# mux-break.net
KiCad netlist of a schematic drawn in EAGLE
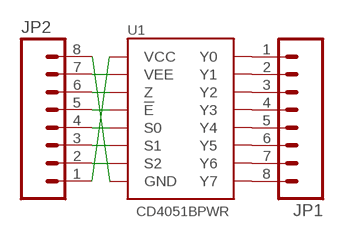
[diagram p0: schematic, sheet 1]

(export (version "E")
  (design (tool "Eeschema 10.0.6"))
  (components
    (comp (ref "JP1")
      (value "M08SILK_FEMALE_PTH")
      (footprint "eagle-import:1X08")
      (libsource (lib "eagle-import") (part "M08SILK_FEMALE_PTH"))
    )
    (comp (ref "JP2")
      (value "M08SILK_FEMALE_PTH")
      (footprint "eagle-import:1X08")
      (libsource (lib "eagle-import") (part "M08SILK_FEMALE_PTH"))
    )
    (comp (ref "U1")
      (value "CD4051BPWR")
      (footprint "eagle-import:TSSOP-16")
      (libsource (lib "eagle-import") (part "CD4051BPWR"))
    )
  )
  (nets
    (net (code "1") (name "Net-(U1-GND)") (class "Default")
      (node (ref "JP2") (pin "8") (pinfunction "8_8") (pintype "passive"))
      (node (ref "U1") (pin "P$8") (pinfunction "GND_P$8") (pintype "bidirectional"))
    )
    (net (code "2") (name "Net-(U1-S0)") (class "Default")
      (node (ref "JP2") (pin "4") (pinfunction "4_4") (pintype "passive"))
      (node (ref "U1") (pin "P$11") (pinfunction "S0_P$11") (pintype "bidirectional"))
    )
    (net (code "3") (name "Net-(U1-S1)") (class "Default")
      (node (ref "JP2") (pin "3") (pinfunction "3_3") (pintype "passive"))
      (node (ref "U1") (pin "P$10") (pinfunction "S1_P$10") (pintype "bidirectional"))
    )
    (net (code "4") (name "Net-(U1-S2)") (class "Default")
      (node (ref "JP2") (pin "2") (pinfunction "2_2") (pintype "passive"))
      (node (ref "U1") (pin "P$9") (pinfunction "S2_P$9") (pintype "bidirectional"))
    )
    (net (code "5") (name "Net-(U1-VCC)") (class "Default")
      (node (ref "JP2") (pin "1") (pinfunction "1_1") (pintype "passive"))
      (node (ref "U1") (pin "P$16") (pinfunction "VCC_P$16") (pintype "bidirectional"))
    )
    (net (code "6") (name "Net-(U1-VEE)") (class "Default")
      (node (ref "JP2") (pin "7") (pinfunction "7_7") (pintype "passive"))
      (node (ref "U1") (pin "P$7") (pinfunction "VEE_P$7") (pintype "bidirectional"))
    )
    (net (code "7") (name "Net-(U1-Y0)") (class "Default")
      (node (ref "JP1") (pin "1") (pinfunction "1_1") (pintype "passive"))
      (node (ref "U1") (pin "P$13") (pinfunction "Y0_P$13") (pintype "bidirectional"))
    )
    (net (code "8") (name "Net-(U1-Y1)") (class "Default")
      (node (ref "JP1") (pin "2") (pinfunction "2_2") (pintype "passive"))
      (node (ref "U1") (pin "P$14") (pinfunction "Y1_P$14") (pintype "bidirectional"))
    )
    (net (code "9") (name "Net-(U1-Y2)") (class "Default")
      (node (ref "JP1") (pin "3") (pinfunction "3_3") (pintype "passive"))
      (node (ref "U1") (pin "P$15") (pinfunction "Y2_P$15") (pintype "bidirectional"))
    )
    (net (code "10") (name "Net-(U1-Y3)") (class "Default")
      (node (ref "JP1") (pin "4") (pinfunction "4_4") (pintype "passive"))
      (node (ref "U1") (pin "P$12") (pinfunction "Y3_P$12") (pintype "bidirectional"))
    )
    (net (code "11") (name "Net-(U1-Y4)") (class "Default")
      (node (ref "JP1") (pin "5") (pinfunction "5_5") (pintype "passive"))
      (node (ref "U1") (pin "P$1") (pinfunction "Y4_P$1") (pintype "bidirectional"))
    )
    (net (code "12") (name "Net-(U1-Y5)") (class "Default")
      (node (ref "JP1") (pin "6") (pinfunction "6_6") (pintype "passive"))
      (node (ref "U1") (pin "P$5") (pinfunction "Y5_P$5") (pintype "bidirectional"))
    )
    (net (code "13") (name "Net-(U1-Y6)") (class "Default")
      (node (ref "JP1") (pin "7") (pinfunction "7_7") (pintype "passive"))
      (node (ref "U1") (pin "P$2") (pinfunction "Y6_P$2") (pintype "bidirectional"))
    )
    (net (code "14") (name "Net-(U1-Y7)") (class "Default")
      (node (ref "JP1") (pin "8") (pinfunction "8_8") (pintype "passive"))
      (node (ref "U1") (pin "P$4") (pinfunction "Y7_P$4") (pintype "bidirectional"))
    )
    (net (code "15") (name "Net-(U1-Z)") (class "Default")
      (node (ref "JP2") (pin "6") (pinfunction "6_6") (pintype "passive"))
      (node (ref "U1") (pin "P$3") (pinfunction "Z_P$3") (pintype "bidirectional"))
    )
    (net (code "16") (name "Net-(U1-~{E})") (class "Default")
      (node (ref "JP2") (pin "5") (pinfunction "5_5") (pintype "passive"))
      (node (ref "U1") (pin "P$6") (pinfunction "~{E}_P$6") (pintype "bidirectional"))
    )
  )
)
